# 1-Controller.net
KiCad netlist of a schematic drawn in Altium Designer
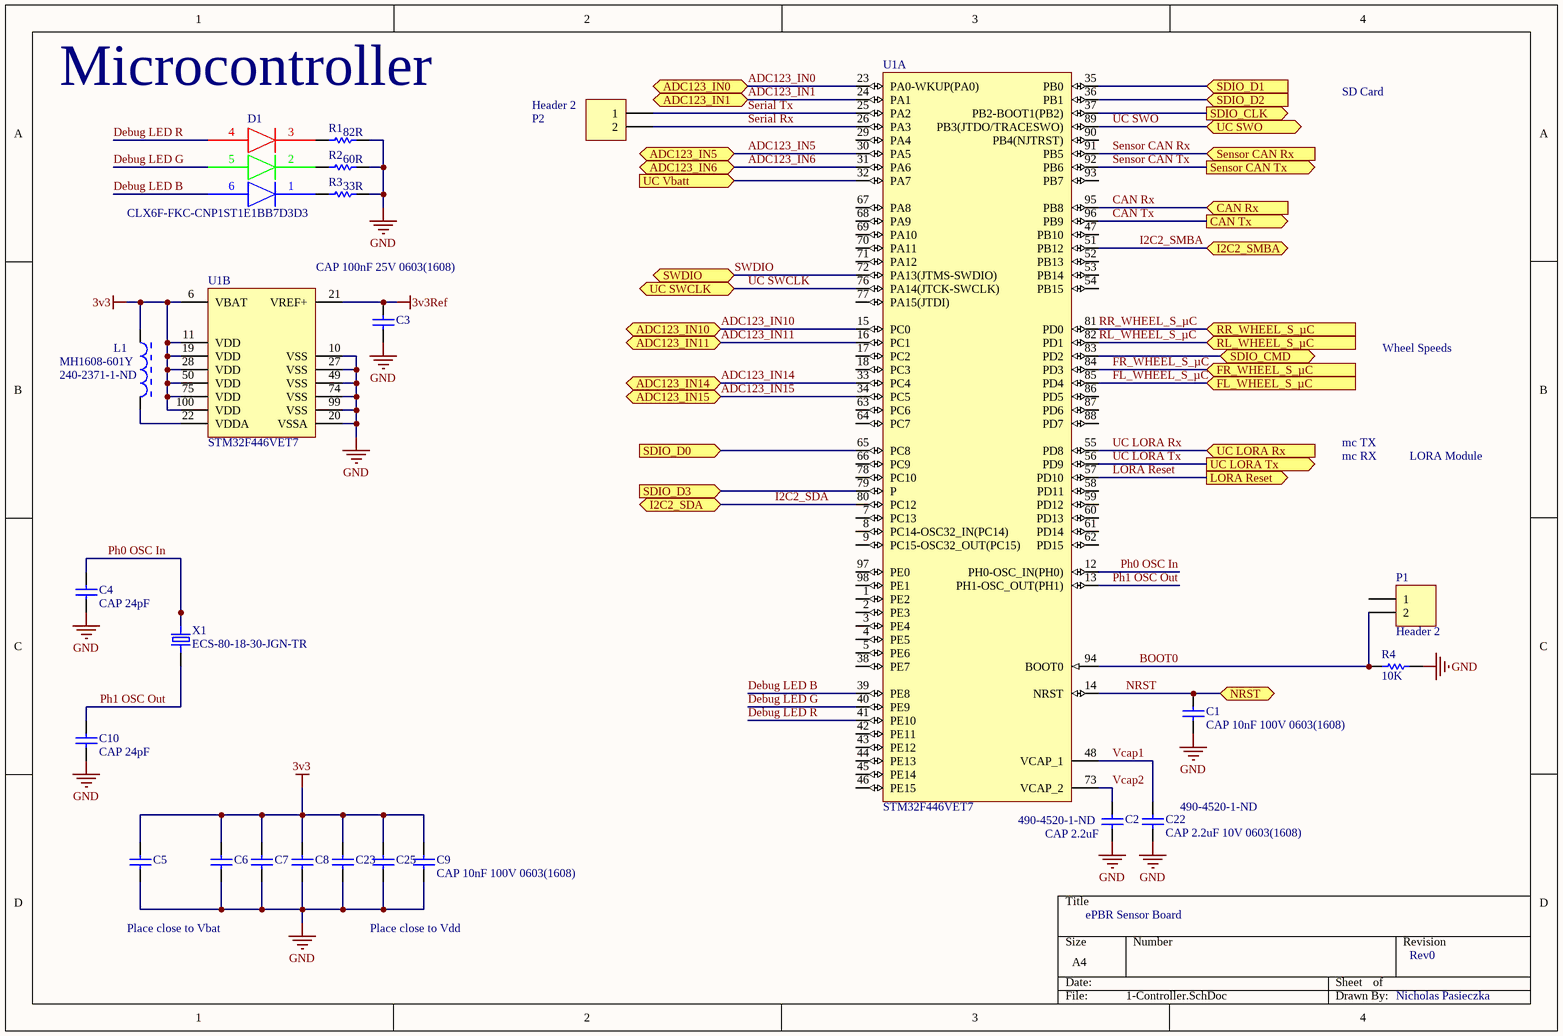
[diagram p0: 1-Controller.SchDoc]

(export (version "E")
  (design (tool "Eeschema 10.0.6"))
  (components
    (comp (ref "C1")
      (value "CAP 10nF 100V 0603(1608)")
      (footprint "CAPC0603(1608)100_M")
      (description "CAP 10nF 100V ±20% 0603 (1608 Metric) Thickness 1mm SMD")
      (fields (field (name "TOLERANCE") "Â±20%"))
      (libsource (lib "ECS-80-18-30-JGN-TR") (part "CAP"))
    )
    (comp (ref "C2")
      (value "CAP 2.2uF")
      (footprint "CAPC0603(1608)55_N")
      (description "CAP 2.2uF 10V ±10% 0603 (1608 Metric) Thickness 0.55mm SMD")
      (fields (field (name "TOLERANCE") "Â±10%") (field (name "SUPPLIER PART NUMBER 1") "490-4520-1-ND"))
      (libsource (lib "Altium Content Vault") (part "CAP"))
    )
    (comp (ref "C3")
      (value "CAP 100nF 25V 0603(1608)")
      (footprint "CAPC0603(1608)100_N")
      (description "CAP 100nF 25V ±20% 0603 (1608 Metric) Thickness 1mm SMD")
      (fields (field (name "TOLERANCE") "Â±20%"))
      (libsource (lib "Altium Content Vault") (part "CAP"))
    )
    (comp (ref "C4")
      (value "CAP 24pF")
      (footprint "CAPC0603(1608)100_N")
      (description "CAP 24pF 16V ±2% 0603 (1608 Metric) Thickness 1mm SMD")
      (fields (field (name "TOLERANCE") "Â±2%"))
      (libsource (lib "Altium Content Vault") (part "CAP"))
    )
    (comp (ref "C5")
      (value "CAP 10nF 100V 0603(1608)")
      (footprint "CAPC0603(1608)100_M")
      (description "CAP 10nF 100V ±20% 0603 (1608 Metric) Thickness 1mm SMD")
      (fields (field (name "TOLERANCE") "Â±20%"))
      (libsource (lib "Altium Content Vault") (part "CAP"))
    )
    (comp (ref "C6")
      (value "CAP 10nF 100V 0603(1608)")
      (footprint "CAPC0603(1608)100_M")
      (description "CAP 10nF 100V ±20% 0603 (1608 Metric) Thickness 1mm SMD")
      (fields (field (name "TOLERANCE") "Â±20%"))
      (libsource (lib "Altium Content Vault") (part "CAP"))
    )
    (comp (ref "C7")
      (value "CAP 10nF 100V 0603(1608)")
      (footprint "CAPC0603(1608)100_M")
      (description "CAP 10nF 100V ±20% 0603 (1608 Metric) Thickness 1mm SMD")
      (fields (field (name "TOLERANCE") "Â±20%"))
      (libsource (lib "Altium Content Vault") (part "CAP"))
    )
    (comp (ref "C8")
      (value "CAP 10nF 100V 0603(1608)")
      (footprint "CAPC0603(1608)100_M")
      (description "CAP 10nF 100V ±20% 0603 (1608 Metric) Thickness 1mm SMD")
      (fields (field (name "TOLERANCE") "Â±20%"))
      (libsource (lib "Altium Content Vault") (part "CAP"))
    )
    (comp (ref "C9")
      (value "CAP 10nF 100V 0603(1608)")
      (footprint "CAPC0603(1608)100_M")
      (description "CAP 10nF 100V ±20% 0603 (1608 Metric) Thickness 1mm SMD")
      (fields (field (name "TOLERANCE") "Â±20%"))
      (libsource (lib "Altium Content Vault") (part "CAP"))
    )
    (comp (ref "C10")
      (value "CAP 24pF")
      (footprint "CAPC0603(1608)100_N")
      (description "CAP 24pF 16V ±2% 0603 (1608 Metric) Thickness 1mm SMD")
      (fields (field (name "TOLERANCE") "Â±2%"))
      (libsource (lib "Altium Content Vault") (part "CAP"))
    )
    (comp (ref "C22")
      (value "CAP 2.2uF 10V 0603(1608)")
      (footprint "CAPC0603(1608)55_N")
      (description "CAP 2.2uF 10V ±10% 0603 (1608 Metric) Thickness 0.55mm SMD")
      (fields (field (name "TOLERANCE") "Â±10%") (field (name "SUPPLIER PART NUMBER 1") "490-4520-1-ND"))
      (libsource (lib "Altium Content Vault") (part "CAP"))
    )
    (comp (ref "C23")
      (value "CAP 10nF 100V 0603(1608)")
      (footprint "CAPC0603(1608)100_M")
      (description "CAP 10nF 100V ±20% 0603 (1608 Metric) Thickness 1mm SMD")
      (fields (field (name "TOLERANCE") "Â±20%"))
      (libsource (lib "Altium Content Vault") (part "CAP"))
    )
    (comp (ref "C25")
      (value "CAP 10nF 100V 0603(1608)")
      (footprint "CAPC0603(1608)100_M")
      (description "CAP 10nF 100V ±20% 0603 (1608 Metric) Thickness 1mm SMD")
      (fields (field (name "TOLERANCE") "Â±20%"))
      (libsource (lib "Altium Content Vault") (part "CAP"))
    )
    (comp (ref "D1")
      (value "CLX6F-FKC-CNP1ST1E1BB7D3D3")
      (footprint "CLX6C-FKB")
      (libsource (lib "VCB_2019") (part "LED - CLX6F-FKC-CNP1ST1E1BB7D3D3"))
    )
    (comp (ref "L1")
      (value "MH1608-601Y")
      (footprint "BOUR-MH1608_V")
      (description "Chip Bead, 600 Ohm, 1 A, -55 to 125 degC, 2-Pin SMD (0603), RoHS, Tape and Reel")
      (fields (field (name "MANUFACTURER") "Bourns") (field (name "SUPPLIER PART NUMBER 1") "240-2371-1-ND"))
      (libsource (lib "Altium Content Vault") (part "IND-FB-2"))
    )
    (comp (ref "P1")
      (value "Header 2")
      (footprint "HDR1X2")
      (description "Header, 2-Pin")
      (fields (field (name "PUBLISHER") "Altium Limited"))
      (libsource (lib "Miscellaneous Connectors") (part "Header 2"))
    )
    (comp (ref "P2")
      (value "Header 2")
      (footprint "HDR1X2")
      (description "Header, 2-Pin")
      (fields (field (name "PUBLISHER") "Altium Limited"))
      (libsource (lib "") (part "Header 2_1"))
    )
    (comp (ref "R1")
      (value "82R")
      (footprint "RESC0603(1608)_N")
      (description "82R 0.1W 5% 0603 (1608 Metric)  SMD")
      (fields (field (name "TOLERANCE") "5 %") (field (name "POWER") "0.1 W"))
      (libsource (lib "Altium Content Vault") (part "RES"))
    )
    (comp (ref "R2")
      (value "60R")
      (footprint "RESC0603(1608)_N")
      (description "60R4 0.1W 1% 0603 (1608 Metric)  SMD")
      (fields (field (name "TOLERANCE") "1 %") (field (name "POWER") "0.1 W"))
      (libsource (lib "Altium Content Vault") (part "RES"))
    )
    (comp (ref "R3")
      (value "33R")
      (footprint "RESC0603(1608)_N")
      (description "33R 0.1W 5% 0603 (1608 Metric)  SMD")
      (fields (field (name "TOLERANCE") "5 %") (field (name "POWER") "0.1 W"))
      (libsource (lib "Altium Content Vault") (part "RES"))
    )
    (comp (ref "R4")
      (value "10K")
      (footprint "RESC0603(1608)_N")
      (description "10K 0.1W 5% 0603 (1608 Metric)  SMD")
      (fields (field (name "TOLERANCE") "5 %") (field (name "POWER") "0.1 W"))
      (libsource (lib "Altium Content Vault") (part "RES"))
    )
    (comp (ref "U1")
      (value "STM32F446VET7")
      (footprint "STM-LQFP100_L")
      (libsource (lib "Altium Content Vault") (part "MC-ARM-STM32F446-LQFP100"))
    )
    (comp (ref "X1")
      (value "ECS-80-18-30-JGN-TR")
      (footprint "SnapEDApcb:XTAL_ECS-80-18-30-JGN-TR")
      (description "8MHz Â±20ppm Crystal 18pF 100 Ohms 2-SMD, No Lead")
      (fields (field (name "DIGI-KEY_PART_NUMBER") "XC2103CT-ND") (field (name "MF") "ECS Inc."))
      (libsource (lib "SnapEDAsch") (part "ECS-80-18-30-JGN-TR"))
    )
  )
  (nets
    (net (code "1") (name "/ADC123_IN0") (class "Default")
      (node (ref "U1") (pin "23") (pinfunction "PA0-WKUP(PA0)_23") (pintype "bidirectional"))
    )
    (net (code "2") (name "/ADC123_IN1") (class "Default")
      (node (ref "U1") (pin "24") (pinfunction "PA1_24") (pintype "bidirectional"))
    )
    (net (code "3") (name "/ADC123_IN5") (class "Default")
      (node (ref "U1") (pin "30") (pinfunction "PA5_30") (pintype "bidirectional"))
    )
    (net (code "4") (name "/ADC123_IN6") (class "Default")
      (node (ref "U1") (pin "31") (pinfunction "PA6_31") (pintype "bidirectional"))
    )
    (net (code "5") (name "/ADC123_IN10") (class "Default")
      (node (ref "U1") (pin "15") (pinfunction "PC0_15") (pintype "bidirectional"))
    )
    (net (code "6") (name "/ADC123_IN11") (class "Default")
      (node (ref "U1") (pin "16") (pinfunction "PC1_16") (pintype "bidirectional"))
    )
    (net (code "7") (name "/ADC123_IN14") (class "Default")
      (node (ref "U1") (pin "33") (pinfunction "PC4_33") (pintype "bidirectional"))
    )
    (net (code "8") (name "/ADC123_IN15") (class "Default")
      (node (ref "U1") (pin "34") (pinfunction "PC5_34") (pintype "bidirectional"))
    )
    (net (code "9") (name "/BOOT0") (class "Default")
      (node (ref "P1") (pin "2") (pinfunction "2_2") (pintype "passive"))
      (node (ref "R4") (pin "1") (pinfunction "1_1") (pintype "passive"))
      (node (ref "U1") (pin "94") (pinfunction "BOOT0_94") (pintype "input"))
    )
    (net (code "10") (name "/CAN Rx") (class "Default")
      (node (ref "U1") (pin "95") (pinfunction "PB8_95") (pintype "bidirectional"))
    )
    (net (code "11") (name "/CAN Tx") (class "Default")
      (node (ref "U1") (pin "96") (pinfunction "PB9_96") (pintype "bidirectional"))
    )
    (net (code "12") (name "/Debug LED B") (class "Default")
      (node (ref "D1") (pin "6") (pinfunction "B_6") (pintype "passive"))
      (node (ref "U1") (pin "39") (pinfunction "PE8_39") (pintype "bidirectional"))
    )
    (net (code "13") (name "/Debug LED G") (class "Default")
      (node (ref "D1") (pin "5") (pinfunction "G_5") (pintype "passive"))
      (node (ref "U1") (pin "40") (pinfunction "PE9_40") (pintype "bidirectional"))
    )
    (net (code "14") (name "/Debug LED R") (class "Default")
      (node (ref "D1") (pin "4") (pinfunction "R_4") (pintype "passive"))
      (node (ref "U1") (pin "41") (pinfunction "PE10_41") (pintype "bidirectional"))
    )
    (net (code "15") (name "/FL_WHEEL_S_µC") (class "Default")
      (node (ref "U1") (pin "85") (pinfunction "PD4_85") (pintype "bidirectional"))
    )
    (net (code "16") (name "/FR_WHEEL_S_µC") (class "Default")
      (node (ref "U1") (pin "84") (pinfunction "PD3_84") (pintype "bidirectional"))
    )
    (net (code "17") (name "/I2C2_SDA") (class "Default")
      (node (ref "U1") (pin "80") (pinfunction "PC12_80") (pintype "bidirectional"))
    )
    (net (code "18") (name "/I2C2_SMBA") (class "Default")
      (node (ref "U1") (pin "51") (pinfunction "PB12_51") (pintype "bidirectional"))
    )
    (net (code "19") (name "/LORA Reset") (class "Default")
      (node (ref "U1") (pin "57") (pinfunction "PD10_57") (pintype "bidirectional"))
    )
    (net (code "20") (name "/NRST") (class "Default")
      (node (ref "C1") (pin "2") (pinfunction "2_2") (pintype "passive"))
      (node (ref "U1") (pin "14") (pinfunction "NRST_14") (pintype "bidirectional"))
    )
    (net (code "21") (name "/Ph0 OSC In") (class "Default")
      (node (ref "C4") (pin "2") (pinfunction "2_2") (pintype "passive"))
      (node (ref "U1") (pin "12") (pinfunction "PH0-OSC_IN(PH0)_12") (pintype "bidirectional"))
      (node (ref "X1") (pin "2") (pinfunction "OUT/IN_2") (pintype "passive"))
    )
    (net (code "22") (name "/Ph1 OSC Out") (class "Default")
      (node (ref "C10") (pin "2") (pinfunction "2_2") (pintype "passive"))
      (node (ref "U1") (pin "13") (pinfunction "PH1-OSC_OUT(PH1)_13") (pintype "bidirectional"))
      (node (ref "X1") (pin "1") (pinfunction "IN/OUT_1") (pintype "passive"))
    )
    (net (code "23") (name "/RL_WHEEL_S_µC") (class "Default")
      (node (ref "U1") (pin "82") (pinfunction "PD1_82") (pintype "bidirectional"))
    )
    (net (code "24") (name "/RR_WHEEL_S_µC") (class "Default")
      (node (ref "U1") (pin "81") (pinfunction "PD0_81") (pintype "bidirectional"))
    )
    (net (code "25") (name "/SDIO_CLK") (class "Default")
      (node (ref "U1") (pin "37") (pinfunction "PB2-BOOT1(PB2)_37") (pintype "bidirectional"))
    )
    (net (code "26") (name "/SDIO_CMD") (class "Default")
      (node (ref "U1") (pin "83") (pinfunction "PD2_83") (pintype "bidirectional"))
    )
    (net (code "27") (name "/SDIO_D0") (class "Default")
      (node (ref "U1") (pin "65") (pinfunction "PC8_65") (pintype "bidirectional"))
    )
    (net (code "28") (name "/SDIO_D1") (class "Default")
      (node (ref "U1") (pin "35") (pinfunction "PB0_35") (pintype "bidirectional"))
    )
    (net (code "29") (name "/SDIO_D2") (class "Default")
      (node (ref "U1") (pin "36") (pinfunction "PB1_36") (pintype "bidirectional"))
    )
    (net (code "30") (name "/SDIO_D3") (class "Default")
      (node (ref "U1") (pin "79") (pinfunction "P_79") (pintype "bidirectional"))
    )
    (net (code "31") (name "/SWDIO") (class "Default")
      (node (ref "U1") (pin "72") (pinfunction "PA13(JTMS-SWDIO)_72") (pintype "bidirectional"))
    )
    (net (code "32") (name "/Sensor CAN Rx") (class "Default")
      (node (ref "U1") (pin "91") (pinfunction "PB5_91") (pintype "bidirectional"))
    )
    (net (code "33") (name "/Sensor CAN Tx") (class "Default")
      (node (ref "U1") (pin "92") (pinfunction "PB6_92") (pintype "bidirectional"))
    )
    (net (code "34") (name "/Serial Rx") (class "Default")
      (node (ref "P2") (pin "2") (pinfunction "2_2") (pintype "passive"))
      (node (ref "U1") (pin "26") (pinfunction "PA3_26") (pintype "bidirectional"))
    )
    (net (code "35") (name "/Serial Tx") (class "Default")
      (node (ref "P2") (pin "1") (pinfunction "1_1") (pintype "passive"))
      (node (ref "U1") (pin "25") (pinfunction "PA2_25") (pintype "bidirectional"))
    )
    (net (code "36") (name "/UC LORA Rx") (class "Default")
      (node (ref "U1") (pin "55") (pinfunction "PD8_55") (pintype "bidirectional"))
    )
    (net (code "37") (name "/UC LORA Tx") (class "Default")
      (node (ref "U1") (pin "56") (pinfunction "PD9_56") (pintype "bidirectional"))
    )
    (net (code "38") (name "/UC SWCLK") (class "Default")
      (node (ref "U1") (pin "76") (pinfunction "PA14(JTCK-SWCLK)_76") (pintype "bidirectional"))
    )
    (net (code "39") (name "/UC SWO") (class "Default")
      (node (ref "U1") (pin "89") (pinfunction "PB3(JTDO/TRACESWO)_89") (pintype "bidirectional"))
    )
    (net (code "40") (name "/UC Vbatt") (class "Default")
      (node (ref "U1") (pin "32") (pinfunction "PA7_32") (pintype "bidirectional"))
    )
    (net (code "41") (name "/Vcap1") (class "Default")
      (node (ref "C22") (pin "2") (pinfunction "2_2") (pintype "passive"))
      (node (ref "U1") (pin "48") (pinfunction "VCAP_1_48") (pintype "passive"))
    )
    (net (code "42") (name "/Vcap2") (class "Default")
      (node (ref "C2") (pin "2") (pinfunction "2_2") (pintype "passive"))
      (node (ref "U1") (pin "73") (pinfunction "VCAP_2_73") (pintype "passive"))
    )
    (net (code "43") (name "3v3") (class "Default")
      (node (ref "C23") (pin "2") (pinfunction "2_2") (pintype "passive"))
      (node (ref "C25") (pin "2") (pinfunction "2_2") (pintype "passive"))
      (node (ref "C5") (pin "2") (pinfunction "2_2") (pintype "passive"))
      (node (ref "C6") (pin "2") (pinfunction "2_2") (pintype "passive"))
      (node (ref "C7") (pin "2") (pinfunction "2_2") (pintype "passive"))
      (node (ref "C8") (pin "2") (pinfunction "2_2") (pintype "passive"))
      (node (ref "C9") (pin "2") (pinfunction "2_2") (pintype "passive"))
      (node (ref "L1") (pin "1") (pinfunction "1_1") (pintype "passive"))
      (node (ref "U1") (pin "100") (pinfunction "VDD_100") (pintype "power_in"))
      (node (ref "U1") (pin "11") (pinfunction "VDD_11") (pintype "power_in"))
      (node (ref "U1") (pin "19") (pinfunction "VDD_19") (pintype "power_in"))
      (node (ref "U1") (pin "28") (pinfunction "VDD_28") (pintype "power_in"))
      (node (ref "U1") (pin "50") (pinfunction "VDD_50") (pintype "power_in"))
      (node (ref "U1") (pin "6") (pinfunction "VBAT_6") (pintype "power_in"))
      (node (ref "U1") (pin "75") (pinfunction "VDD_75") (pintype "power_in"))
    )
    (net (code "44") (name "3v3Ref") (class "Default")
      (node (ref "C3") (pin "2") (pinfunction "2_2") (pintype "passive"))
      (node (ref "U1") (pin "21") (pinfunction "VREF+_21") (pintype "power_in"))
    )
    (net (code "45") (name "GND") (class "Default")
      (node (ref "C1") (pin "1") (pinfunction "1_1") (pintype "passive"))
      (node (ref "C10") (pin "1") (pinfunction "1_1") (pintype "passive"))
      (node (ref "C2") (pin "1") (pinfunction "1_1") (pintype "passive"))
      (node (ref "C22") (pin "1") (pinfunction "1_1") (pintype "passive"))
      (node (ref "C23") (pin "1") (pinfunction "1_1") (pintype "passive"))
      (node (ref "C25") (pin "1") (pinfunction "1_1") (pintype "passive"))
      (node (ref "C3") (pin "1") (pinfunction "1_1") (pintype "passive"))
      (node (ref "C4") (pin "1") (pinfunction "1_1") (pintype "passive"))
      (node (ref "C5") (pin "1") (pinfunction "1_1") (pintype "passive"))
      (node (ref "C6") (pin "1") (pinfunction "1_1") (pintype "passive"))
      (node (ref "C7") (pin "1") (pinfunction "1_1") (pintype "passive"))
      (node (ref "C8") (pin "1") (pinfunction "1_1") (pintype "passive"))
      (node (ref "C9") (pin "1") (pinfunction "1_1") (pintype "passive"))
      (node (ref "R1") (pin "2") (pinfunction "2_2") (pintype "passive"))
      (node (ref "R2") (pin "2") (pinfunction "2_2") (pintype "passive"))
      (node (ref "R3") (pin "2") (pinfunction "2_2") (pintype "passive"))
      (node (ref "R4") (pin "2") (pinfunction "2_2") (pintype "passive"))
      (node (ref "U1") (pin "10") (pinfunction "VSS_10") (pintype "power_in"))
      (node (ref "U1") (pin "20") (pinfunction "VSSA_20") (pintype "power_in"))
      (node (ref "U1") (pin "27") (pinfunction "VSS_27") (pintype "power_in"))
      (node (ref "U1") (pin "49") (pinfunction "VSS_49") (pintype "power_in"))
      (node (ref "U1") (pin "74") (pinfunction "VSS_74") (pintype "power_in"))
      (node (ref "U1") (pin "99") (pinfunction "VSS_99") (pintype "power_in"))
    )
    (net (code "46") (name "Net-(D1-B-Pad1)") (class "Default")
      (node (ref "D1") (pin "1") (pinfunction "B_1") (pintype "passive"))
      (node (ref "R3") (pin "1") (pinfunction "1_1") (pintype "passive"))
    )
    (net (code "47") (name "Net-(D1-G-Pad2)") (class "Default")
      (node (ref "D1") (pin "2") (pinfunction "G_2") (pintype "passive"))
      (node (ref "R2") (pin "1") (pinfunction "1_1") (pintype "passive"))
    )
    (net (code "48") (name "Net-(D1-R-Pad3)") (class "Default")
      (node (ref "D1") (pin "3") (pinfunction "R_3") (pintype "passive"))
      (node (ref "R1") (pin "1") (pinfunction "1_1") (pintype "passive"))
    )
    (net (code "49") (name "Net-(U1B-VDDA)") (class "Default")
      (node (ref "L1") (pin "2") (pinfunction "2_2") (pintype "passive"))
      (node (ref "U1") (pin "22") (pinfunction "VDDA_22") (pintype "power_in"))
    )
    (net (code "50") (name "unconnected-(P1-Pad1)") (class "Default")
      (node (ref "P1") (pin "1") (pinfunction "1_1") (pintype "passive"))
    )
    (net (code "51") (name "unconnected-(U1A-PA4-Pad29)") (class "Default")
      (node (ref "U1") (pin "29") (pinfunction "PA4_29") (pintype "bidirectional"))
    )
    (net (code "52") (name "unconnected-(U1A-PA8-Pad67)") (class "Default")
      (node (ref "U1") (pin "67") (pinfunction "PA8_67") (pintype "bidirectional"))
    )
    (net (code "53") (name "unconnected-(U1A-PA9-Pad68)") (class "Default")
      (node (ref "U1") (pin "68") (pinfunction "PA9_68") (pintype "bidirectional"))
    )
    (net (code "54") (name "unconnected-(U1A-PA10-Pad69)") (class "Default")
      (node (ref "U1") (pin "69") (pinfunction "PA10_69") (pintype "bidirectional"))
    )
    (net (code "55") (name "unconnected-(U1A-PA11-Pad70)") (class "Default")
      (node (ref "U1") (pin "70") (pinfunction "PA11_70") (pintype "bidirectional"))
    )
    (net (code "56") (name "unconnected-(U1A-PA12-Pad71)") (class "Default")
      (node (ref "U1") (pin "71") (pinfunction "PA12_71") (pintype "bidirectional"))
    )
    (net (code "57") (name "unconnected-(U1A-PA15(JTDI)-Pad77)") (class "Default")
      (node (ref "U1") (pin "77") (pinfunction "PA15(JTDI)_77") (pintype "bidirectional"))
    )
    (net (code "58") (name "unconnected-(U1A-PB4(NJTRST)-Pad90)") (class "Default")
      (node (ref "U1") (pin "90") (pinfunction "PB4(NJTRST)_90") (pintype "bidirectional"))
    )
    (net (code "59") (name "unconnected-(U1A-PB7-Pad93)") (class "Default")
      (node (ref "U1") (pin "93") (pinfunction "PB7_93") (pintype "bidirectional"))
    )
    (net (code "60") (name "unconnected-(U1A-PB10-Pad47)") (class "Default")
      (node (ref "U1") (pin "47") (pinfunction "PB10_47") (pintype "bidirectional"))
    )
    (net (code "61") (name "unconnected-(U1A-PB13-Pad52)") (class "Default")
      (node (ref "U1") (pin "52") (pinfunction "PB13_52") (pintype "bidirectional"))
    )
    (net (code "62") (name "unconnected-(U1A-PB14-Pad53)") (class "Default")
      (node (ref "U1") (pin "53") (pinfunction "PB14_53") (pintype "bidirectional"))
    )
    (net (code "63") (name "unconnected-(U1A-PB15-Pad54)") (class "Default")
      (node (ref "U1") (pin "54") (pinfunction "PB15_54") (pintype "bidirectional"))
    )
    (net (code "64") (name "unconnected-(U1A-PC2-Pad17)") (class "Default")
      (node (ref "U1") (pin "17") (pinfunction "PC2_17") (pintype "bidirectional"))
    )
    (net (code "65") (name "unconnected-(U1A-PC3-Pad18)") (class "Default")
      (node (ref "U1") (pin "18") (pinfunction "PC3_18") (pintype "bidirectional"))
    )
    (net (code "66") (name "unconnected-(U1A-PC6-Pad63)") (class "Default")
      (node (ref "U1") (pin "63") (pinfunction "PC6_63") (pintype "bidirectional"))
    )
    (net (code "67") (name "unconnected-(U1A-PC7-Pad64)") (class "Default")
      (node (ref "U1") (pin "64") (pinfunction "PC7_64") (pintype "bidirectional"))
    )
    (net (code "68") (name "unconnected-(U1A-PC9-Pad66)") (class "Default")
      (node (ref "U1") (pin "66") (pinfunction "PC9_66") (pintype "bidirectional"))
    )
    (net (code "69") (name "unconnected-(U1A-PC10-Pad78)") (class "Default")
      (node (ref "U1") (pin "78") (pinfunction "PC10_78") (pintype "bidirectional"))
    )
    (net (code "70") (name "unconnected-(U1A-PC13-Pad7)") (class "Default")
      (node (ref "U1") (pin "7") (pinfunction "PC13_7") (pintype "bidirectional"))
    )
    (net (code "71") (name "unconnected-(U1A-PC14-OSC32_IN(PC14)-Pad8)") (class "Default")
      (node (ref "U1") (pin "8") (pinfunction "PC14-OSC32_IN(PC14)_8") (pintype "bidirectional"))
    )
    (net (code "72") (name "unconnected-(U1A-PC15-OSC32_OUT(PC15)-Pad9)") (class "Default")
      (node (ref "U1") (pin "9") (pinfunction "PC15-OSC32_OUT(PC15)_9") (pintype "bidirectional"))
    )
    (net (code "73") (name "unconnected-(U1A-PD5-Pad86)") (class "Default")
      (node (ref "U1") (pin "86") (pinfunction "PD5_86") (pintype "bidirectional"))
    )
    (net (code "74") (name "unconnected-(U1A-PD6-Pad87)") (class "Default")
      (node (ref "U1") (pin "87") (pinfunction "PD6_87") (pintype "bidirectional"))
    )
    (net (code "75") (name "unconnected-(U1A-PD7-Pad88)") (class "Default")
      (node (ref "U1") (pin "88") (pinfunction "PD7_88") (pintype "bidirectional"))
    )
    (net (code "76") (name "unconnected-(U1A-PD11-Pad58)") (class "Default")
      (node (ref "U1") (pin "58") (pinfunction "PD11_58") (pintype "bidirectional"))
    )
    (net (code "77") (name "unconnected-(U1A-PD12-Pad59)") (class "Default")
      (node (ref "U1") (pin "59") (pinfunction "PD12_59") (pintype "bidirectional"))
    )
    (net (code "78") (name "unconnected-(U1A-PD13-Pad60)") (class "Default")
      (node (ref "U1") (pin "60") (pinfunction "PD13_60") (pintype "bidirectional"))
    )
    (net (code "79") (name "unconnected-(U1A-PD14-Pad61)") (class "Default")
      (node (ref "U1") (pin "61") (pinfunction "PD14_61") (pintype "bidirectional"))
    )
    (net (code "80") (name "unconnected-(U1A-PD15-Pad62)") (class "Default")
      (node (ref "U1") (pin "62") (pinfunction "PD15_62") (pintype "bidirectional"))
    )
    (net (code "81") (name "unconnected-(U1A-PE0-Pad97)") (class "Default")
      (node (ref "U1") (pin "97") (pinfunction "PE0_97") (pintype "bidirectional"))
    )
    (net (code "82") (name "unconnected-(U1A-PE1-Pad98)") (class "Default")
      (node (ref "U1") (pin "98") (pinfunction "PE1_98") (pintype "bidirectional"))
    )
    (net (code "83") (name "unconnected-(U1A-PE2-Pad1)") (class "Default")
      (node (ref "U1") (pin "1") (pinfunction "PE2_1") (pintype "bidirectional"))
    )
    (net (code "84") (name "unconnected-(U1A-PE3-Pad2)") (class "Default")
      (node (ref "U1") (pin "2") (pinfunction "PE3_2") (pintype "bidirectional"))
    )
    (net (code "85") (name "unconnected-(U1A-PE4-Pad3)") (class "Default")
      (node (ref "U1") (pin "3") (pinfunction "PE4_3") (pintype "bidirectional"))
    )
    (net (code "86") (name "unconnected-(U1A-PE5-Pad4)") (class "Default")
      (node (ref "U1") (pin "4") (pinfunction "PE5_4") (pintype "bidirectional"))
    )
    (net (code "87") (name "unconnected-(U1A-PE6-Pad5)") (class "Default")
      (node (ref "U1") (pin "5") (pinfunction "PE6_5") (pintype "bidirectional"))
    )
    (net (code "88") (name "unconnected-(U1A-PE7-Pad38)") (class "Default")
      (node (ref "U1") (pin "38") (pinfunction "PE7_38") (pintype "bidirectional"))
    )
    (net (code "89") (name "unconnected-(U1A-PE11-Pad42)") (class "Default")
      (node (ref "U1") (pin "42") (pinfunction "PE11_42") (pintype "bidirectional"))
    )
    (net (code "90") (name "unconnected-(U1A-PE12-Pad43)") (class "Default")
      (node (ref "U1") (pin "43") (pinfunction "PE12_43") (pintype "bidirectional"))
    )
    (net (code "91") (name "unconnected-(U1A-PE13-Pad44)") (class "Default")
      (node (ref "U1") (pin "44") (pinfunction "PE13_44") (pintype "bidirectional"))
    )
    (net (code "92") (name "unconnected-(U1A-PE14-Pad45)") (class "Default")
      (node (ref "U1") (pin "45") (pinfunction "PE14_45") (pintype "bidirectional"))
    )
    (net (code "93") (name "unconnected-(U1A-PE15-Pad46)") (class "Default")
      (node (ref "U1") (pin "46") (pinfunction "PE15_46") (pintype "bidirectional"))
    )
  )
)
